# 07-SYSTEM_PWR_DIST.net
KiCad netlist of a schematic drawn in Altium Designer
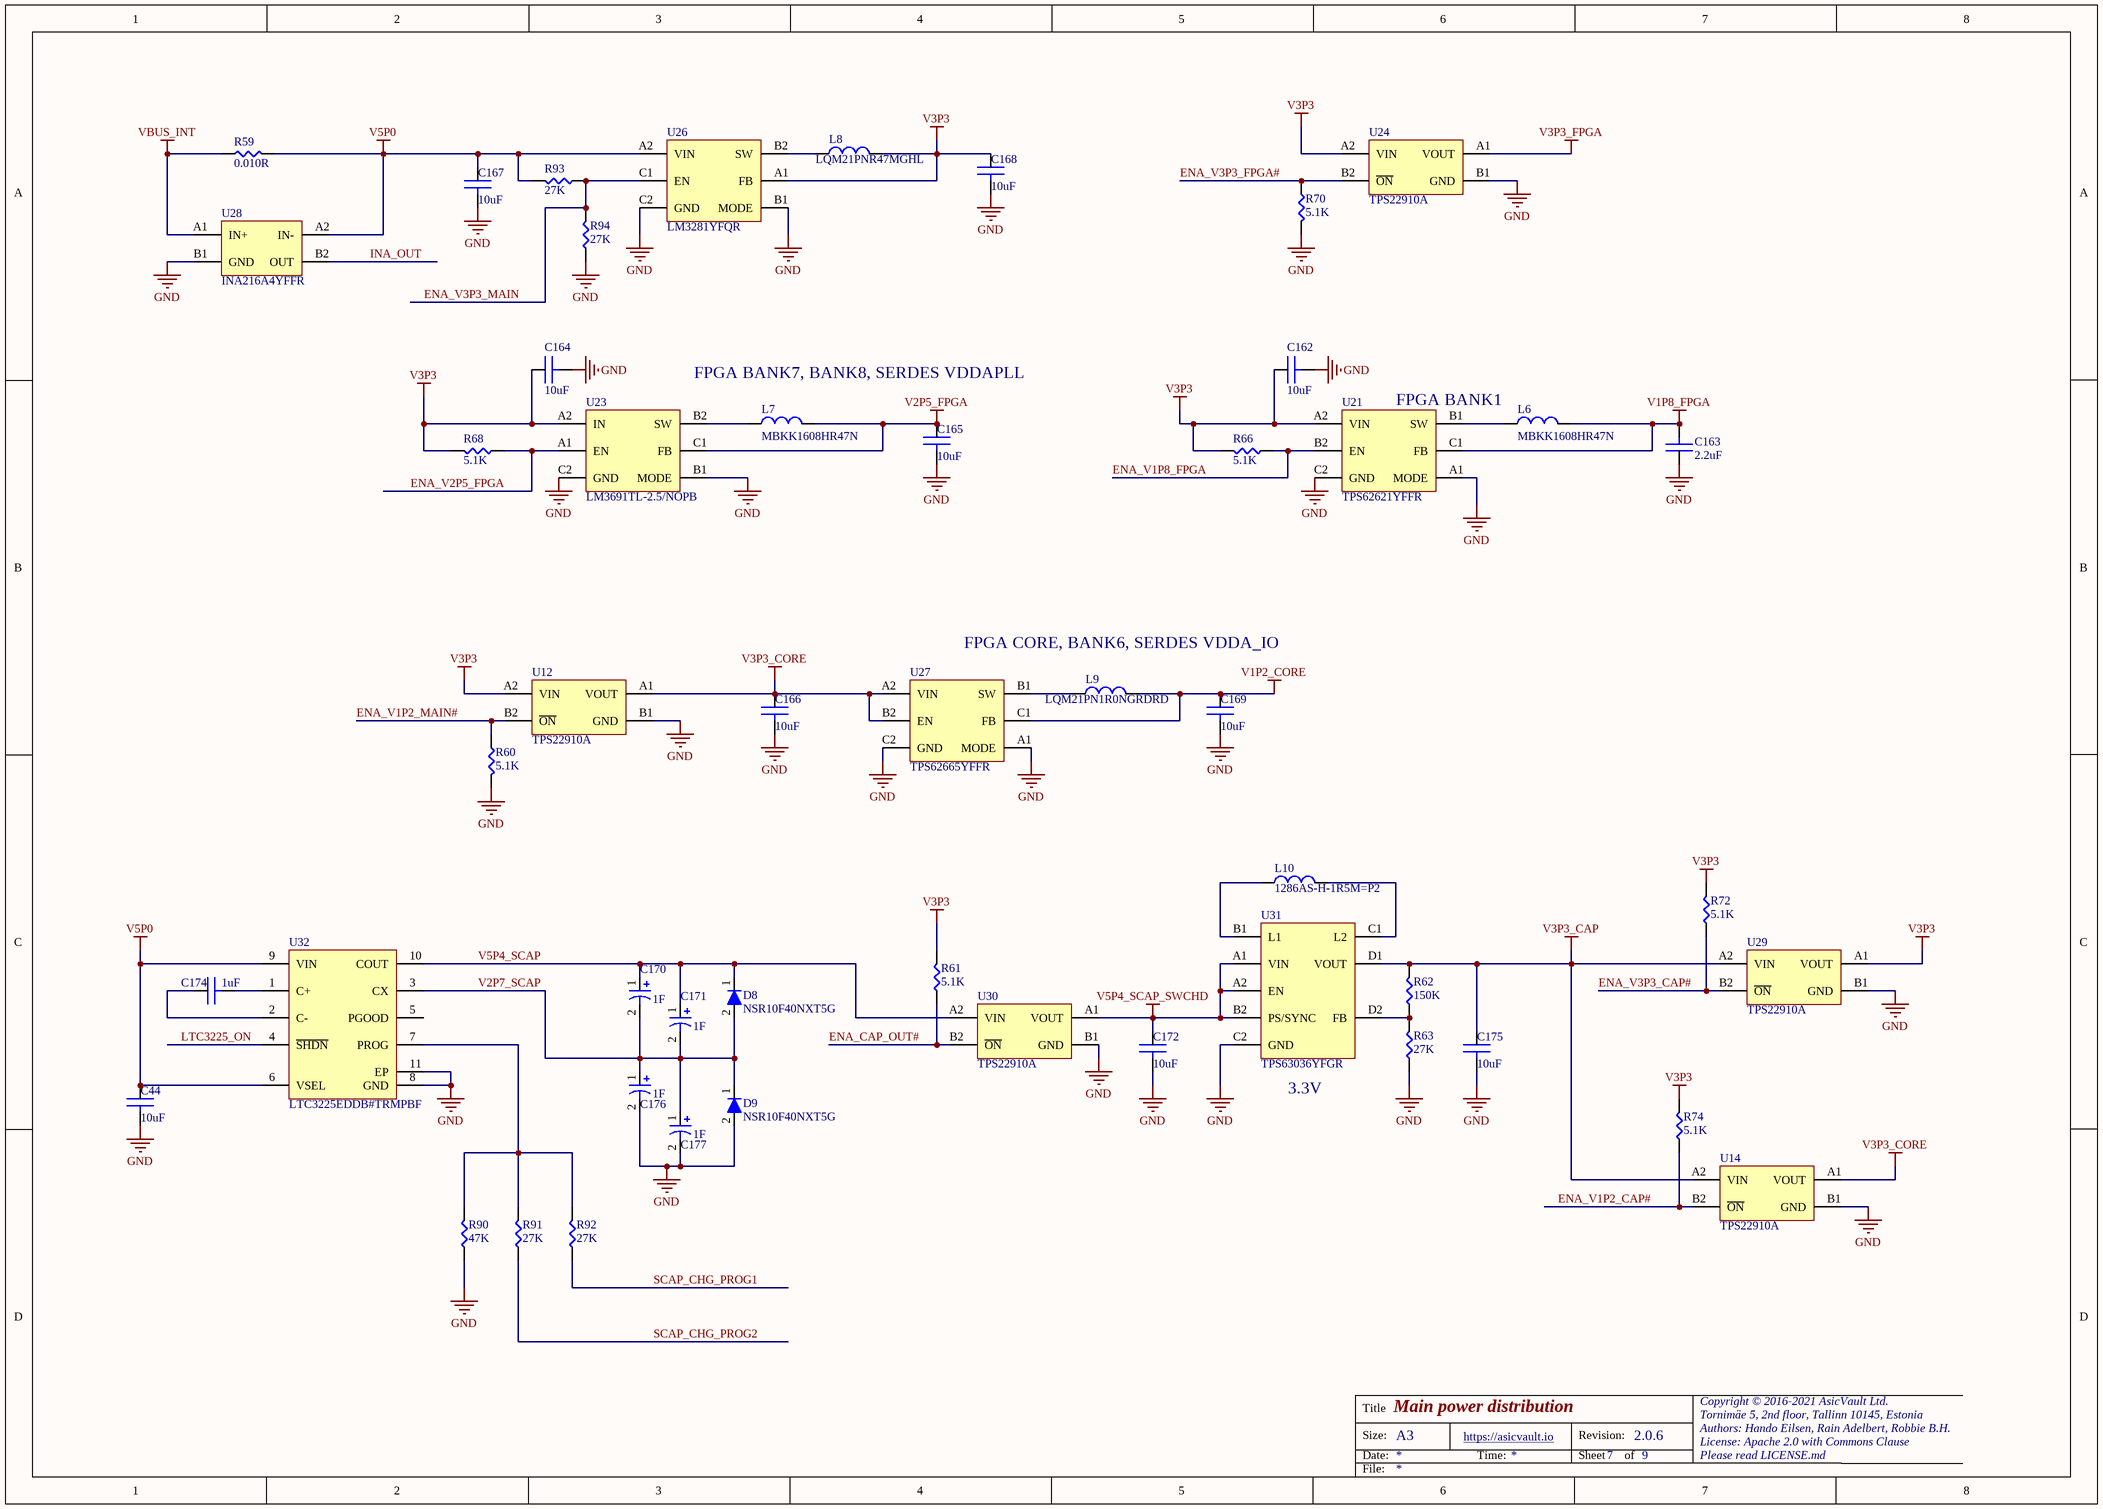
[diagram p0: 07-SYSTEM_PWR_DIST.SchDoc]

(export (version "E")
  (design (tool "Eeschema 10.0.6"))
  (components
    (comp (ref "C44") (value "10uF") (footprint "C0402") (libsource (lib "AMOLED") (part "10uF/0402")))
    (comp (ref "C162") (value "10uF") (footprint "C0402") (libsource (lib "AMOLED") (part "10uF/0402")))
    (comp (ref "C163") (value "2.2uF") (footprint "C0201") (libsource (lib "AMOLED") (part "2.2uF/0201")))
    (comp (ref "C164") (value "10uF") (footprint "C0402") (libsource (lib "AMOLED") (part "10uF/0402")))
    (comp (ref "C165") (value "10uF") (footprint "C0402") (libsource (lib "AMOLED") (part "10uF/0402")))
    (comp (ref "C166") (value "10uF") (footprint "C0402") (libsource (lib "AMOLED") (part "10uF/0402")))
    (comp (ref "C167") (value "10uF") (footprint "C0402") (libsource (lib "AMOLED") (part "10uF/0402")))
    (comp (ref "C168") (value "10uF") (footprint "C0402") (libsource (lib "AMOLED") (part "10uF/0402")))
    (comp (ref "C169") (value "10uF") (footprint "C0402") (libsource (lib "AMOLED") (part "10uF/0402")))
    (comp (ref "C170") (value "1F") (footprint "RB-8*3.5") (libsource (lib "AMOLED") (part "1F")))
    (comp (ref "C171") (value "1F") (footprint "RB-8*3.5") (libsource (lib "AMOLED") (part "1F")))
    (comp (ref "C172") (value "10uF") (footprint "C0402") (libsource (lib "AMOLED") (part "10uF/0402")))
    (comp (ref "C174")
      (value "1uF")
      (footprint "C0201")
      (libsource (lib "AMOLED") (part "1uF/0201/CC0201KRX7R7BB103"))
    )
    (comp (ref "C175") (value "10uF") (footprint "C0402") (libsource (lib "AMOLED") (part "10uF/0402")))
    (comp (ref "C176") (value "1F") (footprint "RB-8*3.5") (libsource (lib "AMOLED") (part "1F")))
    (comp (ref "C177") (value "1F") (footprint "RB-8*3.5") (libsource (lib "AMOLED") (part "1F")))
    (comp (ref "D8")
      (value "NSR10F40NXT5G")
      (footprint "0502")
      (libsource (lib "Control_Board") (part "NSR10F40NXT5G"))
    )
    (comp (ref "D9")
      (value "NSR10F40NXT5G")
      (footprint "0502")
      (libsource (lib "Control_Board") (part "NSR10F40NXT5G"))
    )
    (comp (ref "L6")
      (value "MBKK1608HR47N")
      (footprint "L0603")
      (libsource (lib "AMOLED") (part "0.47uH/MBKK1608HR47N"))
    )
    (comp (ref "L7")
      (value "MBKK1608HR47N")
      (footprint "L0603")
      (libsource (lib "AMOLED") (part "0.47uH/MBKK1608HR47N"))
    )
    (comp (ref "L8")
      (value "LQM21PNR47MGHL")
      (footprint "L0805")
      (libsource (lib "AMOLED") (part "0.47uH/LQM21PNR47MGHL"))
    )
    (comp (ref "L9")
      (value "LQM21PN1R0NGRDRD")
      (footprint "L0805")
      (libsource (lib "AMOLED") (part "1uH/LQM21PN1R0NGRDRD"))
    )
    (comp (ref "L10")
      (value "1286AS-H-1R5M=P2")
      (footprint "DFE201612C")
      (libsource (lib "AMOLED") (part "1.5uH/1286AS-H-1R5M=P2"))
    )
    (comp (ref "R59") (value "0.010R") (footprint "R0603") (libsource (lib "Board3") (part "0.010R/0603")))
    (comp (ref "R60")
      (value "5.1K")
      (footprint "R0201")
      (libsource (lib "Control_Board") (part "5.1K/1%/0201"))
    )
    (comp (ref "R61")
      (value "5.1K")
      (footprint "R0201")
      (libsource (lib "Control_Board") (part "5.1K/1%/0201"))
    )
    (comp (ref "R62")
      (value "150K")
      (footprint "R0201")
      (libsource (lib "Control_Board") (part "150K/1%/0201"))
    )
    (comp (ref "R63")
      (value "27K")
      (footprint "R0201")
      (libsource (lib "Control_Board") (part "27K/1%/0201"))
    )
    (comp (ref "R66")
      (value "5.1K")
      (footprint "R0201")
      (libsource (lib "Control_Board") (part "5.1K/1%/0201"))
    )
    (comp (ref "R68")
      (value "5.1K")
      (footprint "R0201")
      (libsource (lib "Control_Board") (part "5.1K/1%/0201"))
    )
    (comp (ref "R70")
      (value "5.1K")
      (footprint "R0201")
      (libsource (lib "Control_Board") (part "5.1K/1%/0201"))
    )
    (comp (ref "R72")
      (value "5.1K")
      (footprint "R0201")
      (libsource (lib "Control_Board") (part "5.1K/1%/0201"))
    )
    (comp (ref "R74")
      (value "5.1K")
      (footprint "R0201")
      (libsource (lib "Control_Board") (part "5.1K/1%/0201"))
    )
    (comp (ref "R90")
      (value "47K")
      (footprint "R0201")
      (libsource (lib "Control_Board") (part "47K/1%/0201"))
    )
    (comp (ref "R91")
      (value "27K")
      (footprint "R0201")
      (libsource (lib "Control_Board") (part "27K/1%/0201"))
    )
    (comp (ref "R92")
      (value "27K")
      (footprint "R0201")
      (libsource (lib "Control_Board") (part "27K/1%/0201"))
    )
    (comp (ref "R93")
      (value "27K")
      (footprint "R0201")
      (libsource (lib "Control_Board") (part "27K/1%/0201"))
    )
    (comp (ref "R94")
      (value "27K")
      (footprint "R0201")
      (libsource (lib "Control_Board") (part "27K/1%/0201"))
    )
    (comp (ref "U12")
      (value "TPS22910A")
      (footprint "TPS22910A")
      (libsource (lib "AMOLED") (part "TPS22910A"))
    )
    (comp (ref "U14")
      (value "TPS22910A")
      (footprint "TPS22910A")
      (libsource (lib "AMOLED") (part "TPS22910A"))
    )
    (comp (ref "U21")
      (value "TPS62621YFFR")
      (footprint "DSBGA6")
      (libsource (lib "AMOLED") (part "TPS62621YFFR"))
    )
    (comp (ref "U23")
      (value "LM3691TL-2.5/NOPB")
      (footprint "DSBGA6")
      (libsource (lib "AMOLED") (part "LM3691TL-2.5/NOPB"))
    )
    (comp (ref "U24")
      (value "TPS22910A")
      (footprint "TPS22910A")
      (libsource (lib "AMOLED") (part "TPS22910A"))
    )
    (comp (ref "U26")
      (value "LM3281YFQR")
      (footprint "DSBGA6")
      (libsource (lib "AMOLED") (part "LM3281YFQR"))
    )
    (comp (ref "U27")
      (value "TPS62665YFFR")
      (footprint "DSBGA6")
      (libsource (lib "AMOLED") (part "TPS62665YFFR"))
    )
    (comp (ref "U28")
      (value "INA216A4YFFR")
      (footprint "DSBGA4")
      (libsource (lib "AMOLED") (part "INA216A4YFFR"))
    )
    (comp (ref "U29")
      (value "TPS22910A")
      (footprint "TPS22910A")
      (libsource (lib "AMOLED") (part "TPS22910A"))
    )
    (comp (ref "U30")
      (value "TPS22910A")
      (footprint "TPS22910A")
      (libsource (lib "AMOLED") (part "TPS22910A"))
    )
    (comp (ref "U31")
      (value "TPS63036YFGR")
      (footprint "DSBGA8")
      (libsource (lib "AMOLED") (part "TPS63036YFGR"))
    )
    (comp (ref "U32")
      (value "LTC3225EDDB#TRMPBF")
      (footprint "LT-DDB-10_V")
      (libsource (lib "AMOLED") (part "LTC3225EDDB#TRMPBF"))
    )
  )
  (nets
    (net (code "1") (name "/ENA_CAP_OUT#") (class "Default")
      (node (ref "R61") (pin "1") (pinfunction "1_1") (pintype "passive"))
      (node (ref "U30") (pin "B2") (pinfunction "~{ON}_B2") (pintype "passive"))
    )
    (net (code "2") (name "/ENA_V1P2_CAP#") (class "Default")
      (node (ref "R74") (pin "1") (pinfunction "1_1") (pintype "passive"))
      (node (ref "U14") (pin "B2") (pinfunction "~{ON}_B2") (pintype "passive"))
    )
    (net (code "3") (name "/ENA_V1P2_MAIN#") (class "Default")
      (node (ref "R60") (pin "1") (pinfunction "1_1") (pintype "passive"))
      (node (ref "U12") (pin "B2") (pinfunction "~{ON}_B2") (pintype "passive"))
    )
    (net (code "4") (name "/ENA_V1P8_FPGA") (class "Default")
      (node (ref "R66") (pin "1") (pinfunction "1_1") (pintype "passive"))
      (node (ref "U21") (pin "B2") (pinfunction "EN_B2") (pintype "passive"))
    )
    (net (code "5") (name "/ENA_V2P5_FPGA") (class "Default")
      (node (ref "R68") (pin "1") (pinfunction "1_1") (pintype "passive"))
      (node (ref "U23") (pin "A1") (pinfunction "EN_A1") (pintype "passive"))
    )
    (net (code "6") (name "/ENA_V3P3_CAP#") (class "Default")
      (node (ref "R72") (pin "1") (pinfunction "1_1") (pintype "passive"))
      (node (ref "U29") (pin "B2") (pinfunction "~{ON}_B2") (pintype "passive"))
    )
    (net (code "7") (name "/ENA_V3P3_FPGA#") (class "Default")
      (node (ref "R70") (pin "1") (pinfunction "1_1") (pintype "passive"))
      (node (ref "U24") (pin "B2") (pinfunction "~{ON}_B2") (pintype "passive"))
    )
    (net (code "8") (name "/ENA_V3P3_MAIN") (class "Default")
      (node (ref "R93") (pin "1") (pinfunction "1_1") (pintype "passive"))
      (node (ref "R94") (pin "2") (pinfunction "2_2") (pintype "passive"))
      (node (ref "U26") (pin "C1") (pinfunction "EN_C1") (pintype "passive"))
    )
    (net (code "9") (name "/INA_OUT") (class "Default")
      (node (ref "U28") (pin "B2") (pinfunction "OUT_B2") (pintype "passive"))
    )
    (net (code "10") (name "/LTC3225_ON") (class "Default")
      (node (ref "U32") (pin "4") (pinfunction "~{SHDN}_4") (pintype "passive"))
    )
    (net (code "11") (name "/SCAP_CHG_PROG1") (class "Default")
      (node (ref "R92") (pin "1") (pinfunction "1_1") (pintype "passive"))
    )
    (net (code "12") (name "/SCAP_CHG_PROG2") (class "Default")
      (node (ref "R91") (pin "1") (pinfunction "1_1") (pintype "passive"))
    )
    (net (code "13") (name "/V2P7_SCAP") (class "Default")
      (node (ref "C170") (pin "2") (pinfunction "2_2") (pintype "passive"))
      (node (ref "C171") (pin "2") (pinfunction "2_2") (pintype "passive"))
      (node (ref "C176") (pin "1") (pinfunction "1_1") (pintype "passive"))
      (node (ref "C177") (pin "1") (pinfunction "1_1") (pintype "passive"))
      (node (ref "D8") (pin "2") (pinfunction "A_2") (pintype "passive"))
      (node (ref "D9") (pin "1") (pinfunction "K_1") (pintype "passive"))
      (node (ref "U32") (pin "3") (pinfunction "CX_3") (pintype "passive"))
    )
    (net (code "14") (name "/V5P4_SCAP") (class "Default")
      (node (ref "C170") (pin "1") (pinfunction "1_1") (pintype "passive"))
      (node (ref "C171") (pin "1") (pinfunction "1_1") (pintype "passive"))
      (node (ref "D8") (pin "1") (pinfunction "K_1") (pintype "passive"))
      (node (ref "U30") (pin "A2") (pinfunction "VIN_A2") (pintype "passive"))
      (node (ref "U32") (pin "10") (pinfunction "COUT_10") (pintype "passive"))
    )
    (net (code "15") (name "GND") (class "Default")
      (node (ref "C162") (pin "2") (pinfunction "2_2") (pintype "passive"))
      (node (ref "C163") (pin "1") (pinfunction "1_1") (pintype "passive"))
      (node (ref "C164") (pin "2") (pinfunction "2_2") (pintype "passive"))
      (node (ref "C165") (pin "2") (pinfunction "2_2") (pintype "passive"))
      (node (ref "C166") (pin "2") (pinfunction "2_2") (pintype "passive"))
      (node (ref "C167") (pin "2") (pinfunction "2_2") (pintype "passive"))
      (node (ref "C168") (pin "2") (pinfunction "2_2") (pintype "passive"))
      (node (ref "C169") (pin "2") (pinfunction "2_2") (pintype "passive"))
      (node (ref "C172") (pin "2") (pinfunction "2_2") (pintype "passive"))
      (node (ref "C175") (pin "2") (pinfunction "2_2") (pintype "passive"))
      (node (ref "C176") (pin "2") (pinfunction "2_2") (pintype "passive"))
      (node (ref "C177") (pin "2") (pinfunction "2_2") (pintype "passive"))
      (node (ref "C44") (pin "2") (pinfunction "2_2") (pintype "passive"))
      (node (ref "D9") (pin "2") (pinfunction "A_2") (pintype "passive"))
      (node (ref "R60") (pin "2") (pinfunction "2_2") (pintype "passive"))
      (node (ref "R63") (pin "1") (pinfunction "1_1") (pintype "passive"))
      (node (ref "R70") (pin "2") (pinfunction "2_2") (pintype "passive"))
      (node (ref "R90") (pin "1") (pinfunction "1_1") (pintype "passive"))
      (node (ref "R94") (pin "1") (pinfunction "1_1") (pintype "passive"))
      (node (ref "U12") (pin "B1") (pinfunction "GND_B1") (pintype "passive"))
      (node (ref "U14") (pin "B1") (pinfunction "GND_B1") (pintype "passive"))
      (node (ref "U21") (pin "A1") (pinfunction "MODE_A1") (pintype "passive"))
      (node (ref "U21") (pin "C2") (pinfunction "GND_C2") (pintype "passive"))
      (node (ref "U23") (pin "B1") (pinfunction "MODE_B1") (pintype "passive"))
      (node (ref "U23") (pin "C2") (pinfunction "GND_C2") (pintype "passive"))
      (node (ref "U24") (pin "B1") (pinfunction "GND_B1") (pintype "passive"))
      (node (ref "U26") (pin "B1") (pinfunction "MODE_B1") (pintype "passive"))
      (node (ref "U26") (pin "C2") (pinfunction "GND_C2") (pintype "passive"))
      (node (ref "U27") (pin "A1") (pinfunction "MODE_A1") (pintype "passive"))
      (node (ref "U27") (pin "C2") (pinfunction "GND_C2") (pintype "passive"))
      (node (ref "U28") (pin "B1") (pinfunction "GND_B1") (pintype "passive"))
      (node (ref "U29") (pin "B1") (pinfunction "GND_B1") (pintype "passive"))
      (node (ref "U30") (pin "B1") (pinfunction "GND_B1") (pintype "passive"))
      (node (ref "U31") (pin "C2") (pinfunction "GND_C2") (pintype "passive"))
      (node (ref "U32") (pin "11") (pinfunction "EP_11") (pintype "passive"))
      (node (ref "U32") (pin "8") (pinfunction "GND_8") (pintype "passive"))
    )
    (net (code "16") (name "Net-(U21-SW)") (class "Default")
      (node (ref "L6") (pin "1") (pinfunction "1_1") (pintype "passive"))
      (node (ref "U21") (pin "B1") (pinfunction "SW_B1") (pintype "passive"))
    )
    (net (code "17") (name "Net-(U23-SW)") (class "Default")
      (node (ref "L7") (pin "1") (pinfunction "1_1") (pintype "passive"))
      (node (ref "U23") (pin "B2") (pinfunction "SW_B2") (pintype "passive"))
    )
    (net (code "18") (name "Net-(U26-SW)") (class "Default")
      (node (ref "L8") (pin "1") (pinfunction "1_1") (pintype "passive"))
      (node (ref "U26") (pin "B2") (pinfunction "SW_B2") (pintype "passive"))
    )
    (net (code "19") (name "Net-(U27-SW)") (class "Default")
      (node (ref "L9") (pin "1") (pinfunction "1_1") (pintype "passive"))
      (node (ref "U27") (pin "B1") (pinfunction "SW_B1") (pintype "passive"))
    )
    (net (code "20") (name "Net-(U31-FB)") (class "Default")
      (node (ref "R62") (pin "1") (pinfunction "1_1") (pintype "passive"))
      (node (ref "R63") (pin "2") (pinfunction "2_2") (pintype "passive"))
      (node (ref "U31") (pin "D2") (pinfunction "FB_D2") (pintype "passive"))
    )
    (net (code "21") (name "Net-(U31-L1)") (class "Default")
      (node (ref "L10") (pin "1") (pinfunction "1_1") (pintype "passive"))
      (node (ref "U31") (pin "B1") (pinfunction "L1_B1") (pintype "passive"))
    )
    (net (code "22") (name "Net-(U31-L2)") (class "Default")
      (node (ref "L10") (pin "2") (pinfunction "2_2") (pintype "passive"))
      (node (ref "U31") (pin "C1") (pinfunction "L2_C1") (pintype "passive"))
    )
    (net (code "23") (name "Net-(U32-C+)") (class "Default")
      (node (ref "C174") (pin "2") (pinfunction "2_2") (pintype "passive"))
      (node (ref "U32") (pin "1") (pinfunction "C+_1") (pintype "passive"))
    )
    (net (code "24") (name "Net-(U32-C-)") (class "Default")
      (node (ref "C174") (pin "1") (pinfunction "1_1") (pintype "passive"))
      (node (ref "U32") (pin "2") (pinfunction "C-_2") (pintype "passive"))
    )
    (net (code "25") (name "Net-(U32-PROG)") (class "Default")
      (node (ref "R90") (pin "2") (pinfunction "2_2") (pintype "passive"))
      (node (ref "R91") (pin "2") (pinfunction "2_2") (pintype "passive"))
      (node (ref "R92") (pin "2") (pinfunction "2_2") (pintype "passive"))
      (node (ref "U32") (pin "7") (pinfunction "PROG_7") (pintype "passive"))
    )
    (net (code "26") (name "V1P2_CORE") (class "Default")
      (node (ref "C169") (pin "1") (pinfunction "1_1") (pintype "passive"))
      (node (ref "L9") (pin "2") (pinfunction "2_2") (pintype "passive"))
      (node (ref "U27") (pin "C1") (pinfunction "FB_C1") (pintype "passive"))
    )
    (net (code "27") (name "V1P8_FPGA") (class "Default")
      (node (ref "C163") (pin "2") (pinfunction "2_2") (pintype "passive"))
      (node (ref "L6") (pin "2") (pinfunction "2_2") (pintype "passive"))
      (node (ref "U21") (pin "C1") (pinfunction "FB_C1") (pintype "passive"))
    )
    (net (code "28") (name "V2P5_FPGA") (class "Default")
      (node (ref "C165") (pin "1") (pinfunction "1_1") (pintype "passive"))
      (node (ref "L7") (pin "2") (pinfunction "2_2") (pintype "passive"))
      (node (ref "U23") (pin "C1") (pinfunction "FB_C1") (pintype "passive"))
    )
    (net (code "29") (name "V3P3") (class "Default")
      (node (ref "C162") (pin "1") (pinfunction "1_1") (pintype "passive"))
      (node (ref "C164") (pin "1") (pinfunction "1_1") (pintype "passive"))
      (node (ref "C168") (pin "1") (pinfunction "1_1") (pintype "passive"))
      (node (ref "L8") (pin "2") (pinfunction "2_2") (pintype "passive"))
      (node (ref "R61") (pin "2") (pinfunction "2_2") (pintype "passive"))
      (node (ref "R66") (pin "2") (pinfunction "2_2") (pintype "passive"))
      (node (ref "R68") (pin "2") (pinfunction "2_2") (pintype "passive"))
      (node (ref "R72") (pin "2") (pinfunction "2_2") (pintype "passive"))
      (node (ref "R74") (pin "2") (pinfunction "2_2") (pintype "passive"))
      (node (ref "U12") (pin "A2") (pinfunction "VIN_A2") (pintype "passive"))
      (node (ref "U21") (pin "A2") (pinfunction "VIN_A2") (pintype "passive"))
      (node (ref "U23") (pin "A2") (pinfunction "IN_A2") (pintype "passive"))
      (node (ref "U24") (pin "A2") (pinfunction "VIN_A2") (pintype "passive"))
      (node (ref "U26") (pin "A1") (pinfunction "FB_A1") (pintype "passive"))
      (node (ref "U29") (pin "A1") (pinfunction "VOUT_A1") (pintype "passive"))
    )
    (net (code "30") (name "V3P3_CAP") (class "Default")
      (node (ref "C175") (pin "1") (pinfunction "1_1") (pintype "passive"))
      (node (ref "R62") (pin "2") (pinfunction "2_2") (pintype "passive"))
      (node (ref "U14") (pin "A2") (pinfunction "VIN_A2") (pintype "passive"))
      (node (ref "U29") (pin "A2") (pinfunction "VIN_A2") (pintype "passive"))
      (node (ref "U31") (pin "D1") (pinfunction "VOUT_D1") (pintype "passive"))
    )
    (net (code "31") (name "V3P3_CORE") (class "Default")
      (node (ref "C166") (pin "1") (pinfunction "1_1") (pintype "passive"))
      (node (ref "U12") (pin "A1") (pinfunction "VOUT_A1") (pintype "passive"))
      (node (ref "U14") (pin "A1") (pinfunction "VOUT_A1") (pintype "passive"))
      (node (ref "U27") (pin "A2") (pinfunction "VIN_A2") (pintype "passive"))
      (node (ref "U27") (pin "B2") (pinfunction "EN_B2") (pintype "passive"))
    )
    (net (code "32") (name "V3P3_FPGA") (class "Default")
      (node (ref "U24") (pin "A1") (pinfunction "VOUT_A1") (pintype "passive"))
    )
    (net (code "33") (name "V5P0") (class "Default")
      (node (ref "C167") (pin "1") (pinfunction "1_1") (pintype "passive"))
      (node (ref "C44") (pin "1") (pinfunction "1_1") (pintype "passive"))
      (node (ref "R59") (pin "2") (pinfunction "2_2") (pintype "passive"))
      (node (ref "R93") (pin "2") (pinfunction "2_2") (pintype "passive"))
      (node (ref "U26") (pin "A2") (pinfunction "VIN_A2") (pintype "passive"))
      (node (ref "U28") (pin "A2") (pinfunction "IN-_A2") (pintype "passive"))
      (node (ref "U32") (pin "6") (pinfunction "VSEL_6") (pintype "passive"))
      (node (ref "U32") (pin "9") (pinfunction "VIN_9") (pintype "passive"))
    )
    (net (code "34") (name "V5P4_SCAP_SWCHD") (class "Default")
      (node (ref "C172") (pin "1") (pinfunction "1_1") (pintype "passive"))
      (node (ref "U30") (pin "A1") (pinfunction "VOUT_A1") (pintype "passive"))
      (node (ref "U31") (pin "A1") (pinfunction "VIN_A1") (pintype "passive"))
      (node (ref "U31") (pin "A2") (pinfunction "EN_A2") (pintype "passive"))
      (node (ref "U31") (pin "B2") (pinfunction "PS/SYNC_B2") (pintype "passive"))
    )
    (net (code "35") (name "VBUS_INT") (class "Default")
      (node (ref "R59") (pin "1") (pinfunction "1_1") (pintype "passive"))
      (node (ref "U28") (pin "A1") (pinfunction "IN+_A1") (pintype "passive"))
    )
    (net (code "36") (name "unconnected-(U32-PGOOD-Pad5)") (class "Default")
      (node (ref "U32") (pin "5") (pinfunction "PGOOD_5") (pintype "passive"))
    )
  )
)
